# GlucometerV2_1.net
KiCad netlist of a schematic drawn in EAGLE
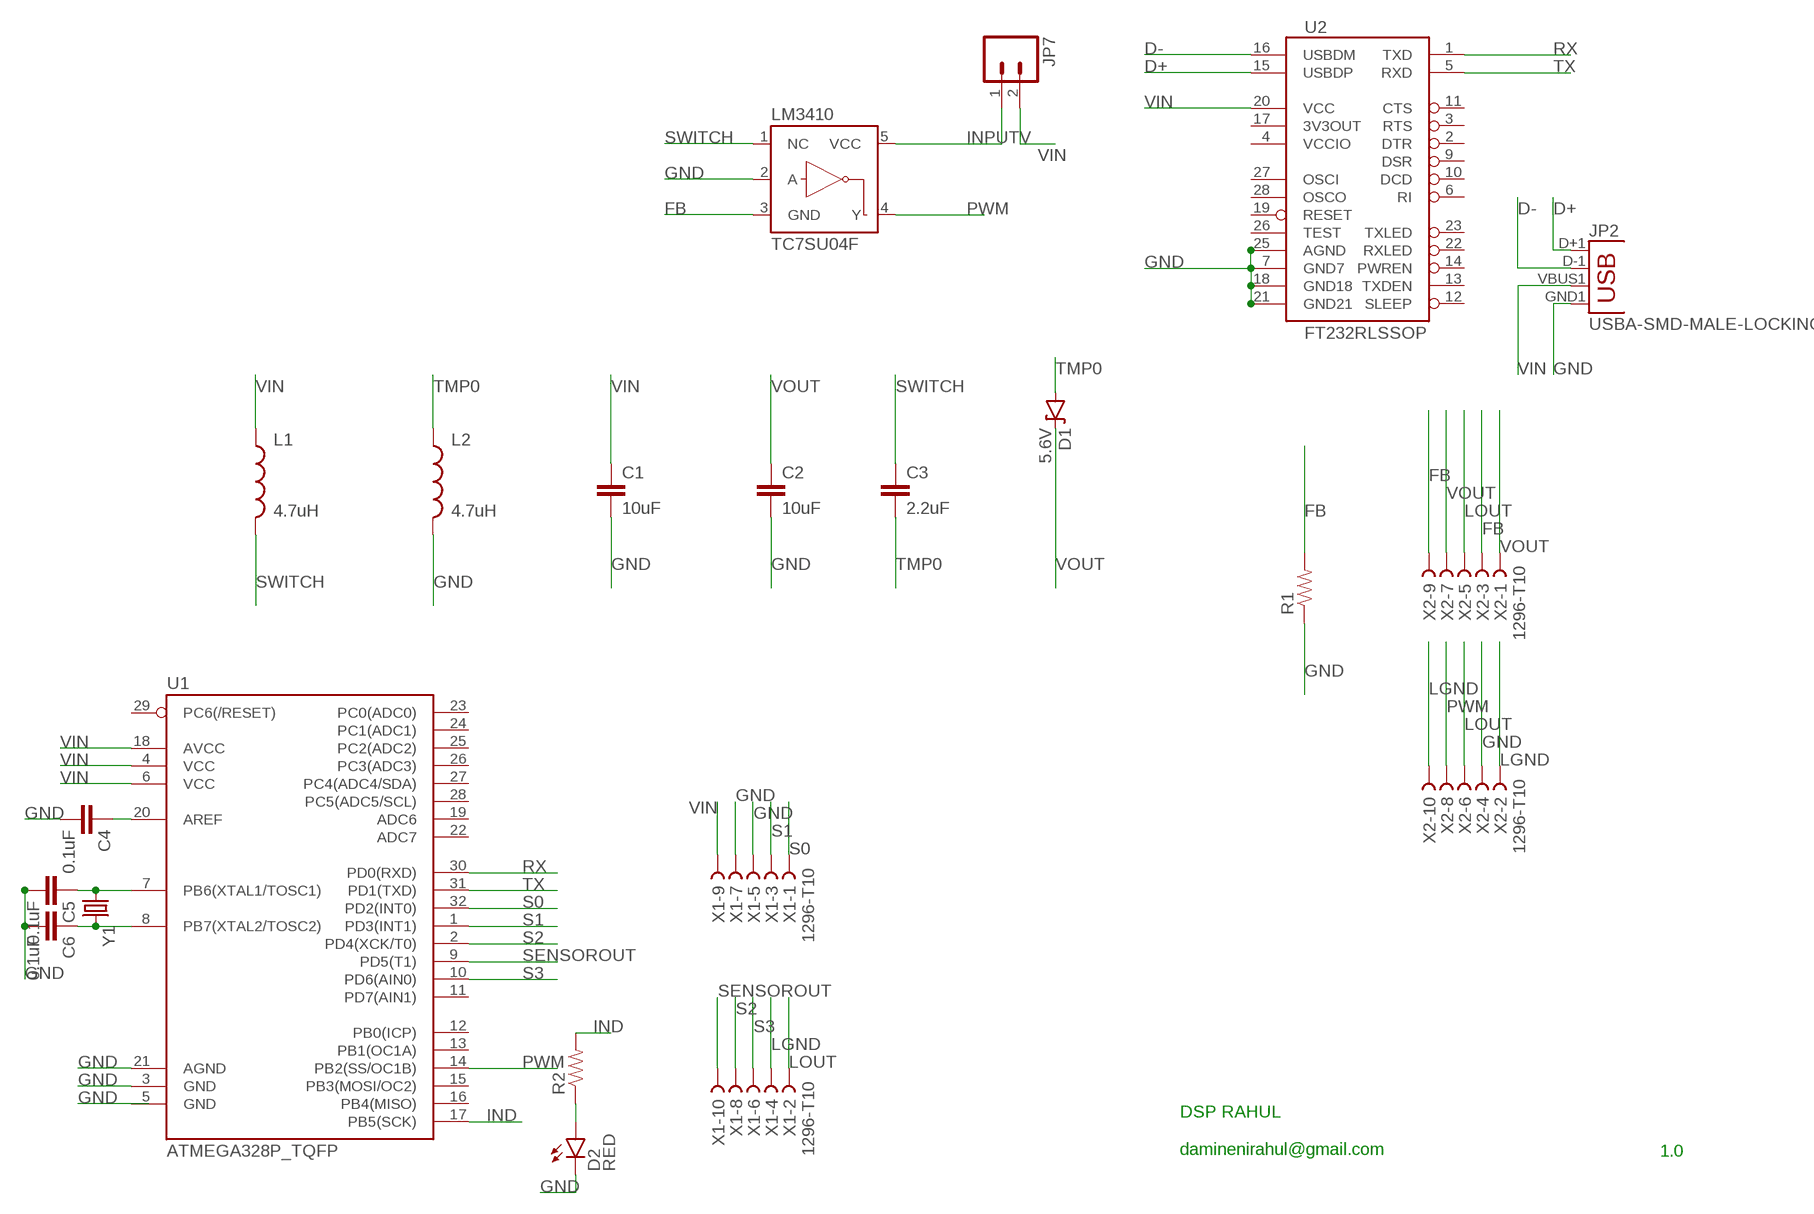
[diagram p0: schematic, sheet 1]

(export (version "E")
  (design (tool "Eeschema 10.0.6"))
  (components
    (comp (ref "C1")
      (value "10uF")
      (footprint "eagle-import:1206")
      (libsource (lib "eagle-import") (part "CAP1206"))
    )
    (comp (ref "C2")
      (value "10uF")
      (footprint "eagle-import:1206")
      (libsource (lib "eagle-import") (part "CAP1206"))
    )
    (comp (ref "C3")
      (value "2.2uF")
      (footprint "eagle-import:1206")
      (libsource (lib "eagle-import") (part "CAP1206"))
    )
    (comp (ref "C4")
      (value "0.1uF")
      (footprint "eagle-import:0603-CAP")
      (libsource (lib "eagle-import") (part "0.1UF-25V(+80/-20%)(0603)"))
    )
    (comp (ref "C5")
      (value "0.1uF")
      (footprint "eagle-import:0603-CAP")
      (libsource (lib "eagle-import") (part "0.1UF-25V(+80/-20%)(0603)"))
    )
    (comp (ref "C6")
      (value "0.1uF")
      (footprint "eagle-import:0603-CAP")
      (libsource (lib "eagle-import") (part "0.1UF-25V(+80/-20%)(0603)"))
    )
    (comp (ref "D1")
      (value "5.6V")
      (footprint "eagle-import:SOD-323")
      (libsource (lib "eagle-import") (part "DIODE-ZENER5.6V"))
    )
    (comp (ref "D2")
      (value "RED")
      (footprint "eagle-import:LED-1206")
      (libsource (lib "eagle-import") (part "LED-RED1206"))
    )
    (comp (ref "JP2")
      (value "USBA-SMD-MALE-LOCKING")
      (footprint "eagle-import:USB-A-SMT-MALE-LOCKING")
      (libsource (lib "eagle-import") (part "USBA-SMD-MALE-LOCKING"))
    )
    (comp (ref "JP7")
      (value "M02POLAR_LOCK")
      (footprint "eagle-import:MOLEX-1X2_LOCK")
      (libsource (lib "eagle-import") (part "M02POLAR_LOCK"))
    )
    (comp (ref "L1")
      (value "4.7uH")
      (footprint "eagle-import:0603")
      (libsource (lib "eagle-import") (part "INDUCTOR30OHM,1.8A"))
    )
    (comp (ref "L2")
      (value "4.7uH")
      (footprint "eagle-import:0603")
      (libsource (lib "eagle-import") (part "INDUCTOR30OHM,1.8A"))
    )
    (comp (ref "LM3410")
      (value "TC7SU04F")
      (footprint "eagle-import:SOT23-5")
      (libsource (lib "eagle-import") (part "INVERTER_SOT23-5"))
    )
    (comp (ref "R1")
      (value "RESISTOR1206")
      (footprint "eagle-import:1206")
      (libsource (lib "eagle-import") (part "RESISTOR1206"))
    )
    (comp (ref "R2")
      (value "RESISTOR1206")
      (footprint "eagle-import:1206")
      (libsource (lib "eagle-import") (part "RESISTOR1206"))
    )
    (comp (ref "U1")
      (value "ATMEGA328P_TQFP")
      (footprint "eagle-import:TQFP32-08")
      (libsource (lib "eagle-import") (part "ATMEGA328P_TQFP"))
    )
    (comp (ref "U2")
      (value "FT232RLSSOP")
      (footprint "eagle-import:SSOP28DB")
      (libsource (lib "eagle-import") (part "FT232RLSSOP"))
    )
    (comp (ref "X1")
      (value "1296-T10")
      (footprint "eagle-import:1296-10")
      (libsource (lib "eagle-import") (part "1296-T10"))
    )
    (comp (ref "X2")
      (value "1296-T10")
      (footprint "eagle-import:1296-10")
      (libsource (lib "eagle-import") (part "1296-T10"))
    )
    (comp (ref "Y1")
      (value "CRYSTALHC49UV")
      (footprint "eagle-import:HC49U-V")
      (libsource (lib "eagle-import") (part "CRYSTALHC49UV"))
    )
  )
  (nets
    (net (code "1") (name "/D+") (class "Default")
      (node (ref "JP2") (pin "D+1") (pinfunction "D+_D+1") (pintype "bidirectional"))
      (node (ref "U2") (pin "15") (pinfunction "USBDP_15") (pintype "bidirectional"))
    )
    (net (code "2") (name "/D-") (class "Default")
      (node (ref "JP2") (pin "D-1") (pinfunction "D-_D-1") (pintype "bidirectional"))
      (node (ref "U2") (pin "16") (pinfunction "USBDM_16") (pintype "bidirectional"))
    )
    (net (code "3") (name "/FB") (class "Default")
      (node (ref "LM3410") (pin "3") (pinfunction "GND_3") (pintype "bidirectional"))
      (node (ref "R1") (pin "2") (pinfunction "2_2") (pintype "passive"))
      (node (ref "X2") (pin "3") (pinfunction "B_3") (pintype "passive"))
      (node (ref "X2") (pin "9") (pinfunction "B_9") (pintype "passive"))
    )
    (net (code "4") (name "/GND") (class "Default")
      (node (ref "C1") (pin "2") (pinfunction "2_2") (pintype "passive"))
      (node (ref "C2") (pin "2") (pinfunction "2_2") (pintype "passive"))
      (node (ref "C4") (pin "2") (pinfunction "2_2") (pintype "passive"))
      (node (ref "C5") (pin "2") (pinfunction "2_2") (pintype "passive"))
      (node (ref "C6") (pin "2") (pinfunction "2_2") (pintype "passive"))
      (node (ref "D2") (pin "C") (pinfunction "C_C") (pintype "passive"))
      (node (ref "JP2") (pin "GND1") (pinfunction "GND_GND1") (pintype "bidirectional"))
      (node (ref "L2") (pin "2") (pinfunction "2_2") (pintype "passive"))
      (node (ref "LM3410") (pin "2") (pinfunction "A_2") (pintype "bidirectional"))
      (node (ref "R1") (pin "1") (pinfunction "1_1") (pintype "passive"))
      (node (ref "U1") (pin "21") (pinfunction "AGND_21") (pintype "bidirectional"))
      (node (ref "U1") (pin "3") (pinfunction "GND_3") (pintype "bidirectional"))
      (node (ref "U2") (pin "18") (pinfunction "GND18_18") (pintype "power_in"))
      (node (ref "U2") (pin "21") (pinfunction "GND21_21") (pintype "power_in"))
      (node (ref "U2") (pin "25") (pinfunction "AGND_25") (pintype "power_in"))
      (node (ref "U2") (pin "7") (pinfunction "GND7_7") (pintype "power_in"))
      (node (ref "X1") (pin "5") (pinfunction "B_5") (pintype "passive"))
      (node (ref "X1") (pin "7") (pinfunction "B_7") (pintype "passive"))
      (node (ref "X2") (pin "4") (pinfunction "B_4") (pintype "passive"))
    )
    (net (code "5") (name "/IND") (class "Default")
      (node (ref "R2") (pin "2") (pinfunction "2_2") (pintype "passive"))
      (node (ref "U1") (pin "17") (pinfunction "PB5(SCK)_17") (pintype "bidirectional"))
    )
    (net (code "6") (name "/INPUTV") (class "Default")
      (node (ref "JP7") (pin "1") (pinfunction "1_1") (pintype "passive"))
      (node (ref "LM3410") (pin "5") (pinfunction "VCC_5") (pintype "bidirectional"))
    )
    (net (code "7") (name "/LGND") (class "Default")
      (node (ref "X1") (pin "4") (pinfunction "B_4") (pintype "passive"))
      (node (ref "X2") (pin "10") (pinfunction "B_10") (pintype "passive"))
      (node (ref "X2") (pin "2") (pinfunction "B_2") (pintype "passive"))
    )
    (net (code "8") (name "/LOUT") (class "Default")
      (node (ref "X1") (pin "2") (pinfunction "B_2") (pintype "passive"))
      (node (ref "X2") (pin "5") (pinfunction "B_5") (pintype "passive"))
      (node (ref "X2") (pin "6") (pinfunction "B_6") (pintype "passive"))
    )
    (net (code "9") (name "/PWM") (class "Default")
      (node (ref "LM3410") (pin "4") (pinfunction "Y_4") (pintype "bidirectional"))
      (node (ref "U1") (pin "14") (pinfunction "PB2(SS/OC1B)_14") (pintype "bidirectional"))
      (node (ref "X2") (pin "8") (pinfunction "B_8") (pintype "passive"))
    )
    (net (code "10") (name "/RX") (class "Default")
      (node (ref "U1") (pin "30") (pinfunction "PD0(RXD)_30") (pintype "bidirectional"))
      (node (ref "U2") (pin "1") (pinfunction "TXD_1") (pintype "output"))
    )
    (net (code "11") (name "/S0") (class "Default")
      (node (ref "U1") (pin "32") (pinfunction "PD2(INT0)_32") (pintype "bidirectional"))
      (node (ref "X1") (pin "1") (pinfunction "B_1") (pintype "passive"))
    )
    (net (code "12") (name "/S1") (class "Default")
      (node (ref "U1") (pin "1") (pinfunction "PD3(INT1)_1") (pintype "bidirectional"))
      (node (ref "X1") (pin "3") (pinfunction "B_3") (pintype "passive"))
    )
    (net (code "13") (name "/S2") (class "Default")
      (node (ref "U1") (pin "2") (pinfunction "PD4(XCK/T0)_2") (pintype "bidirectional"))
      (node (ref "X1") (pin "8") (pinfunction "B_8") (pintype "passive"))
    )
    (net (code "14") (name "/S3") (class "Default")
      (node (ref "U1") (pin "10") (pinfunction "PD6(AIN0)_10") (pintype "bidirectional"))
      (node (ref "X1") (pin "6") (pinfunction "B_6") (pintype "passive"))
    )
    (net (code "15") (name "/SENSOROUT") (class "Default")
      (node (ref "U1") (pin "9") (pinfunction "PD5(T1)_9") (pintype "bidirectional"))
      (node (ref "X1") (pin "10") (pinfunction "B_10") (pintype "passive"))
    )
    (net (code "16") (name "/SWITCH") (class "Default")
      (node (ref "C3") (pin "1") (pinfunction "1_1") (pintype "passive"))
      (node (ref "L1") (pin "2") (pinfunction "2_2") (pintype "passive"))
      (node (ref "LM3410") (pin "1") (pinfunction "NC_1") (pintype "bidirectional"))
    )
    (net (code "17") (name "/TMP0") (class "Default")
      (node (ref "C3") (pin "2") (pinfunction "2_2") (pintype "passive"))
      (node (ref "D1") (pin "A") (pinfunction "A_A") (pintype "passive"))
      (node (ref "L2") (pin "1") (pinfunction "1_1") (pintype "passive"))
    )
    (net (code "18") (name "/TX") (class "Default")
      (node (ref "U1") (pin "31") (pinfunction "PD1(TXD)_31") (pintype "bidirectional"))
      (node (ref "U2") (pin "5") (pinfunction "RXD_5") (pintype "input"))
    )
    (net (code "19") (name "/VCCIO") (class "Default")
      (node (ref "U2") (pin "4") (pinfunction "VCCIO_4") (pintype "power_in"))
    )
    (net (code "20") (name "/VIN") (class "Default")
      (node (ref "C1") (pin "1") (pinfunction "1_1") (pintype "passive"))
      (node (ref "JP2") (pin "VBUS1") (pinfunction "VBUS_VBUS1") (pintype "bidirectional"))
      (node (ref "JP7") (pin "2") (pinfunction "2_2") (pintype "passive"))
      (node (ref "L1") (pin "1") (pinfunction "1_1") (pintype "passive"))
      (node (ref "U1") (pin "18") (pinfunction "AVCC_18") (pintype "bidirectional"))
      (node (ref "U1") (pin "4") (pinfunction "VCC_4") (pintype "bidirectional"))
      (node (ref "U1") (pin "6") (pinfunction "VCC_6") (pintype "bidirectional"))
      (node (ref "U2") (pin "20") (pinfunction "VCC_20") (pintype "power_in"))
      (node (ref "X1") (pin "9") (pinfunction "B_9") (pintype "passive"))
    )
    (net (code "21") (name "/VOUT") (class "Default")
      (node (ref "C2") (pin "1") (pinfunction "1_1") (pintype "passive"))
      (node (ref "D1") (pin "C") (pinfunction "C_C") (pintype "passive"))
      (node (ref "X2") (pin "1") (pinfunction "B_1") (pintype "passive"))
      (node (ref "X2") (pin "7") (pinfunction "B_7") (pintype "passive"))
    )
    (net (code "22") (name "Net-(D2-PadA)") (class "Default")
      (node (ref "D2") (pin "A") (pinfunction "A_A") (pintype "passive"))
      (node (ref "R2") (pin "1") (pinfunction "1_1") (pintype "passive"))
    )
    (net (code "23") (name "Net-(U1-AREF)") (class "Default")
      (node (ref "C4") (pin "1") (pinfunction "1_1") (pintype "passive"))
      (node (ref "U1") (pin "20") (pinfunction "AREF_20") (pintype "bidirectional"))
    )
    (net (code "24") (name "Net-(U1-PB6(XTAL1{slash}TOSC1))") (class "Default")
      (node (ref "C5") (pin "1") (pinfunction "1_1") (pintype "passive"))
      (node (ref "U1") (pin "7") (pinfunction "PB6(XTAL1/TOSC1)_7") (pintype "bidirectional"))
      (node (ref "Y1") (pin "1") (pinfunction "1_1") (pintype "passive"))
    )
    (net (code "25") (name "Net-(U1-PB7(XTAL2{slash}TOSC2))") (class "Default")
      (node (ref "C6") (pin "1") (pinfunction "1_1") (pintype "passive"))
      (node (ref "U1") (pin "8") (pinfunction "PB7(XTAL2/TOSC2)_8") (pintype "bidirectional"))
      (node (ref "Y1") (pin "2") (pinfunction "2_2") (pintype "passive"))
    )
    (net (code "26") (name "unconnected-(U1-ADC6-Pad19)") (class "Default")
      (node (ref "U1") (pin "19") (pinfunction "ADC6_19") (pintype "bidirectional"))
    )
    (net (code "27") (name "unconnected-(U1-ADC7-Pad22)") (class "Default")
      (node (ref "U1") (pin "22") (pinfunction "ADC7_22") (pintype "bidirectional"))
    )
    (net (code "28") (name "unconnected-(U1-GND-Pad5)") (class "Default")
      (node (ref "U1") (pin "5") (pinfunction "GND_5") (pintype "bidirectional"))
    )
    (net (code "29") (name "unconnected-(U1-PB0(ICP)-Pad12)") (class "Default")
      (node (ref "U1") (pin "12") (pinfunction "PB0(ICP)_12") (pintype "bidirectional"))
    )
    (net (code "30") (name "unconnected-(U1-PB1(OC1A)-Pad13)") (class "Default")
      (node (ref "U1") (pin "13") (pinfunction "PB1(OC1A)_13") (pintype "bidirectional"))
    )
    (net (code "31") (name "unconnected-(U1-PB3(MOSI{slash}OC2)-Pad15)") (class "Default")
      (node (ref "U1") (pin "15") (pinfunction "PB3(MOSI/OC2)_15") (pintype "bidirectional"))
    )
    (net (code "32") (name "unconnected-(U1-PB4(MISO)-Pad16)") (class "Default")
      (node (ref "U1") (pin "16") (pinfunction "PB4(MISO)_16") (pintype "bidirectional"))
    )
    (net (code "33") (name "unconnected-(U1-PC0(ADC0)-Pad23)") (class "Default")
      (node (ref "U1") (pin "23") (pinfunction "PC0(ADC0)_23") (pintype "bidirectional"))
    )
    (net (code "34") (name "unconnected-(U1-PC1(ADC1)-Pad24)") (class "Default")
      (node (ref "U1") (pin "24") (pinfunction "PC1(ADC1)_24") (pintype "bidirectional"))
    )
    (net (code "35") (name "unconnected-(U1-PC2(ADC2)-Pad25)") (class "Default")
      (node (ref "U1") (pin "25") (pinfunction "PC2(ADC2)_25") (pintype "bidirectional"))
    )
    (net (code "36") (name "unconnected-(U1-PC3(ADC3)-Pad26)") (class "Default")
      (node (ref "U1") (pin "26") (pinfunction "PC3(ADC3)_26") (pintype "bidirectional"))
    )
    (net (code "37") (name "unconnected-(U1-PC4(ADC4{slash}SDA)-Pad27)") (class "Default")
      (node (ref "U1") (pin "27") (pinfunction "PC4(ADC4/SDA)_27") (pintype "bidirectional"))
    )
    (net (code "38") (name "unconnected-(U1-PC5(ADC5{slash}SCL)-Pad28)") (class "Default")
      (node (ref "U1") (pin "28") (pinfunction "PC5(ADC5/SCL)_28") (pintype "bidirectional"))
    )
    (net (code "39") (name "unconnected-(U1-PC6({slash}RESET)-Pad29)") (class "Default")
      (node (ref "U1") (pin "29") (pinfunction "PC6(/RESET)_29") (pintype "bidirectional"))
    )
    (net (code "40") (name "unconnected-(U1-PD7(AIN1)-Pad11)") (class "Default")
      (node (ref "U1") (pin "11") (pinfunction "PD7(AIN1)_11") (pintype "bidirectional"))
    )
    (net (code "41") (name "unconnected-(U2-3V3OUT-Pad17)") (class "Default")
      (node (ref "U2") (pin "17") (pinfunction "3V3OUT_17") (pintype "output"))
    )
    (net (code "42") (name "unconnected-(U2-CTS-Pad11)") (class "Default")
      (node (ref "U2") (pin "11") (pinfunction "CTS_11") (pintype "input"))
    )
    (net (code "43") (name "unconnected-(U2-DCD-Pad10)") (class "Default")
      (node (ref "U2") (pin "10") (pinfunction "DCD_10") (pintype "input"))
    )
    (net (code "44") (name "unconnected-(U2-DSR-Pad9)") (class "Default")
      (node (ref "U2") (pin "9") (pinfunction "DSR_9") (pintype "input"))
    )
    (net (code "45") (name "unconnected-(U2-DTR-Pad2)") (class "Default")
      (node (ref "U2") (pin "2") (pinfunction "DTR_2") (pintype "output"))
    )
    (net (code "46") (name "unconnected-(U2-OSCI-Pad27)") (class "Default")
      (node (ref "U2") (pin "27") (pinfunction "OSCI_27") (pintype "input"))
    )
    (net (code "47") (name "unconnected-(U2-OSCO-Pad28)") (class "Default")
      (node (ref "U2") (pin "28") (pinfunction "OSCO_28") (pintype "output"))
    )
    (net (code "48") (name "unconnected-(U2-PWREN-Pad14)") (class "Default")
      (node (ref "U2") (pin "14") (pinfunction "PWREN_14") (pintype "input"))
    )
    (net (code "49") (name "unconnected-(U2-RESET-Pad19)") (class "Default")
      (node (ref "U2") (pin "19") (pinfunction "RESET_19") (pintype "input"))
    )
    (net (code "50") (name "unconnected-(U2-RI-Pad6)") (class "Default")
      (node (ref "U2") (pin "6") (pinfunction "RI_6") (pintype "input"))
    )
    (net (code "51") (name "unconnected-(U2-RTS-Pad3)") (class "Default")
      (node (ref "U2") (pin "3") (pinfunction "RTS_3") (pintype "output"))
    )
    (net (code "52") (name "unconnected-(U2-RXLED-Pad22)") (class "Default")
      (node (ref "U2") (pin "22") (pinfunction "RXLED_22") (pintype "input"))
    )
    (net (code "53") (name "unconnected-(U2-SLEEP-Pad12)") (class "Default")
      (node (ref "U2") (pin "12") (pinfunction "SLEEP_12") (pintype "input"))
    )
    (net (code "54") (name "unconnected-(U2-TEST-Pad26)") (class "Default")
      (node (ref "U2") (pin "26") (pinfunction "TEST_26") (pintype "input"))
    )
    (net (code "55") (name "unconnected-(U2-TXDEN-Pad13)") (class "Default")
      (node (ref "U2") (pin "13") (pinfunction "TXDEN_13") (pintype "input"))
    )
    (net (code "56") (name "unconnected-(U2-TXLED-Pad23)") (class "Default")
      (node (ref "U2") (pin "23") (pinfunction "TXLED_23") (pintype "input"))
    )
  )
)
